# Schematic.net
KiCad netlist of a schematic drawn in EAGLE
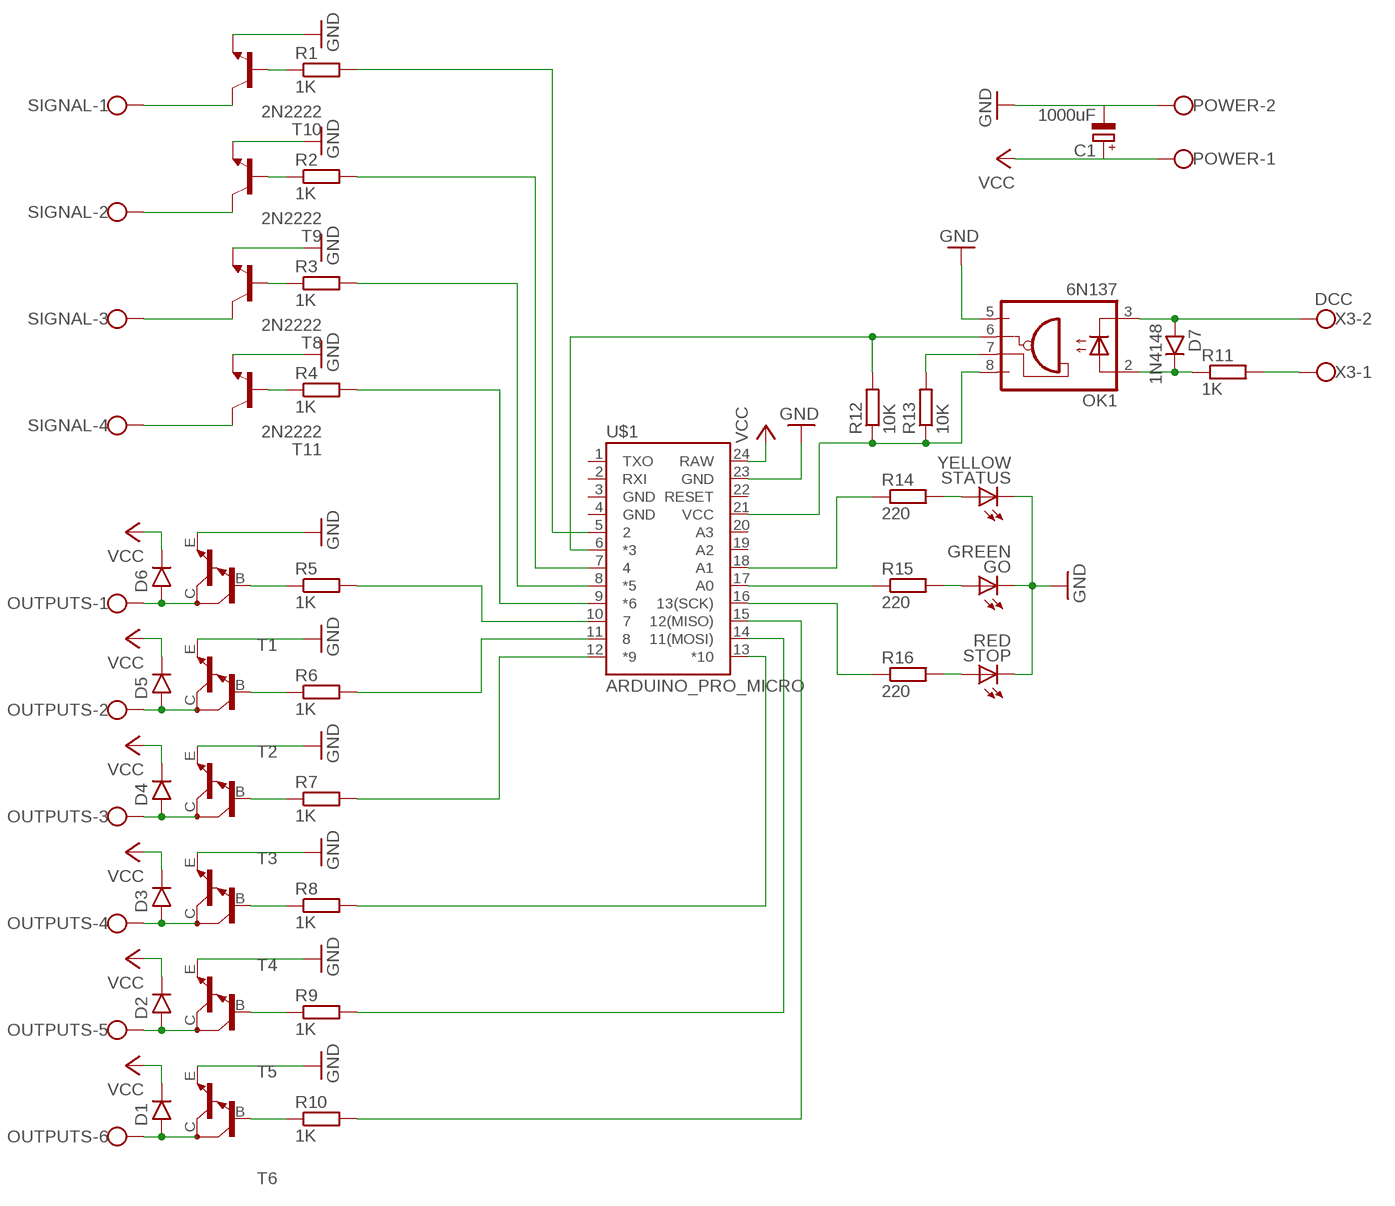
[diagram p0: schematic, sheet 1]

(export (version "E")
  (design (tool "Eeschema 10.0.6"))
  (components
    (comp (ref "C1")
      (value "1000uF")
      (footprint "eagle-import:E5-13")
      (libsource (lib "eagle-import") (part "CPOL-EUE5-13"))
    )
    (comp (ref "D1")
      (value "DO41.3")
      (footprint "eagle-import:DO41-3")
      (libsource (lib "eagle-import") (part "DO41.3"))
    )
    (comp (ref "D2")
      (value "DO41.3")
      (footprint "eagle-import:DO41-3")
      (libsource (lib "eagle-import") (part "DO41.3"))
    )
    (comp (ref "D3")
      (value "DO41.3")
      (footprint "eagle-import:DO41-3")
      (libsource (lib "eagle-import") (part "DO41.3"))
    )
    (comp (ref "D4")
      (value "DO41.3")
      (footprint "eagle-import:DO41-3")
      (libsource (lib "eagle-import") (part "DO41.3"))
    )
    (comp (ref "D5")
      (value "DO41.3")
      (footprint "eagle-import:DO41-3")
      (libsource (lib "eagle-import") (part "DO41.3"))
    )
    (comp (ref "D6")
      (value "DO41.3")
      (footprint "eagle-import:DO41-3")
      (libsource (lib "eagle-import") (part "DO41.3"))
    )
    (comp (ref "D7")
      (value "1N4148")
      (footprint "eagle-import:DO35-3")
      (libsource (lib "eagle-import") (part "1N914.3"))
    )
    (comp (ref "GO")
      (value "GREEN")
      (footprint "eagle-import:LED3MM")
      (libsource (lib "eagle-import") (part "LED3MM"))
    )
    (comp (ref "OK1")
      (value "6N137")
      (footprint "eagle-import:DIL08")
      (libsource (lib "eagle-import") (part "6N137"))
    )
    (comp (ref "OUTPUTS")
      (value "W237-6")
      (footprint "eagle-import:W237-6")
      (libsource (lib "eagle-import") (part "W237-6"))
    )
    (comp (ref "POWER")
      (value "W237-102")
      (footprint "eagle-import:W237-102")
      (fields (field (name "MPN") "237-102"))
      (libsource (lib "eagle-import") (part "W237-102"))
    )
    (comp (ref "R1")
      (value "1K")
      (footprint "eagle-import:0204_7")
      (libsource (lib "eagle-import") (part "R-EU_0204/7"))
    )
    (comp (ref "R2")
      (value "1K")
      (footprint "eagle-import:0204_7")
      (libsource (lib "eagle-import") (part "R-EU_0204/7"))
    )
    (comp (ref "R3")
      (value "1K")
      (footprint "eagle-import:0204_7")
      (libsource (lib "eagle-import") (part "R-EU_0204/7"))
    )
    (comp (ref "R4")
      (value "1K")
      (footprint "eagle-import:0204_7")
      (libsource (lib "eagle-import") (part "R-EU_0204/7"))
    )
    (comp (ref "R5")
      (value "1K")
      (footprint "eagle-import:0204_7")
      (libsource (lib "eagle-import") (part "R-EU_0204/7"))
    )
    (comp (ref "R6")
      (value "1K")
      (footprint "eagle-import:0204_7")
      (libsource (lib "eagle-import") (part "R-EU_0204/7"))
    )
    (comp (ref "R7")
      (value "1K")
      (footprint "eagle-import:0204_7")
      (libsource (lib "eagle-import") (part "R-EU_0204/7"))
    )
    (comp (ref "R8")
      (value "1K")
      (footprint "eagle-import:0204_7")
      (libsource (lib "eagle-import") (part "R-EU_0204/7"))
    )
    (comp (ref "R9")
      (value "1K")
      (footprint "eagle-import:0204_7")
      (libsource (lib "eagle-import") (part "R-EU_0204/7"))
    )
    (comp (ref "R10")
      (value "1K")
      (footprint "eagle-import:0204_7")
      (libsource (lib "eagle-import") (part "R-EU_0204/7"))
    )
    (comp (ref "R11")
      (value "1K")
      (footprint "eagle-import:0204_7")
      (libsource (lib "eagle-import") (part "resistor_R-EU_0204/7"))
    )
    (comp (ref "R12")
      (value "10K")
      (footprint "eagle-import:0204_7")
      (libsource (lib "eagle-import") (part "resistor_R-EU_0204/7"))
    )
    (comp (ref "R13")
      (value "10K")
      (footprint "eagle-import:0204_7")
      (libsource (lib "eagle-import") (part "resistor_R-EU_0204/7"))
    )
    (comp (ref "R14")
      (value "220")
      (footprint "eagle-import:0204_7")
      (libsource (lib "eagle-import") (part "R-EU_0204/7"))
    )
    (comp (ref "R15")
      (value "220")
      (footprint "eagle-import:0204_7")
      (libsource (lib "eagle-import") (part "R-EU_0204/7"))
    )
    (comp (ref "R16")
      (value "220")
      (footprint "eagle-import:0204_7")
      (libsource (lib "eagle-import") (part "R-EU_0204/7"))
    )
    (comp (ref "SIGNAL")
      (value "W237-4")
      (footprint "eagle-import:W237-4")
      (libsource (lib "eagle-import") (part "W237-4"))
    )
    (comp (ref "STATUS")
      (value "YELLOW")
      (footprint "eagle-import:LED3MM")
      (libsource (lib "eagle-import") (part "LED3MM"))
    )
    (comp (ref "STOP")
      (value "RED")
      (footprint "eagle-import:LED3MM")
      (libsource (lib "eagle-import") (part "LED3MM"))
    )
    (comp (ref "T1")
      (value "TIP122VERTICAL")
      (footprint "eagle-import:TO220AV")
      (libsource (lib "eagle-import") (part "TIP122VERTICAL"))
    )
    (comp (ref "T2")
      (value "TIP122VERTICAL")
      (footprint "eagle-import:TO220AV")
      (libsource (lib "eagle-import") (part "TIP122VERTICAL"))
    )
    (comp (ref "T3")
      (value "TIP122VERTICAL")
      (footprint "eagle-import:TO220AV")
      (libsource (lib "eagle-import") (part "TIP122VERTICAL"))
    )
    (comp (ref "T4")
      (value "TIP122VERTICAL")
      (footprint "eagle-import:TO220AV")
      (libsource (lib "eagle-import") (part "TIP122VERTICAL"))
    )
    (comp (ref "T5")
      (value "TIP122VERTICAL")
      (footprint "eagle-import:TO220AV")
      (libsource (lib "eagle-import") (part "TIP122VERTICAL"))
    )
    (comp (ref "T6")
      (value "TIP122VERTICAL")
      (footprint "eagle-import:TO220AV")
      (libsource (lib "eagle-import") (part "TIP122VERTICAL"))
    )
    (comp (ref "T8")
      (value "2N2222")
      (footprint "eagle-import:TO92-EBC")
      (libsource (lib "eagle-import") (part "-NPN-TO92-EBC"))
    )
    (comp (ref "T9")
      (value "2N2222")
      (footprint "eagle-import:TO92-EBC")
      (libsource (lib "eagle-import") (part "-NPN-TO92-EBC"))
    )
    (comp (ref "T10")
      (value "2N2222")
      (footprint "eagle-import:TO92-EBC")
      (libsource (lib "eagle-import") (part "-NPN-TO92-EBC"))
    )
    (comp (ref "T11")
      (value "2N2222")
      (footprint "eagle-import:TO92-EBC")
      (libsource (lib "eagle-import") (part "-NPN-TO92-EBC"))
    )
    (comp (ref "U$1")
      (value "ARDUINO_PRO_MICRO")
      (footprint "eagle-import:ARDUINO_PRO_MICRO")
      (libsource (lib "eagle-import") (part "ARDUINO_PRO_MICRO"))
    )
    (comp (ref "X3")
      (value "DCC")
      (footprint "eagle-import:W237-102")
      (fields (field (name "MPN") "237-102"))
      (libsource (lib "eagle-import") (part "W237-102"))
    )
  )
  (nets
    (net (code "1") (name "GND") (class "Default")
      (node (ref "C1") (pin "-") (pinfunction "-_-") (pintype "passive"))
      (node (ref "GO") (pin "K") (pinfunction "C_K") (pintype "passive"))
      (node (ref "OK1") (pin "5") (pinfunction "GND_5") (pintype "passive"))
      (node (ref "POWER") (pin "2") (pinfunction "KL_2") (pintype "passive"))
      (node (ref "STATUS") (pin "K") (pinfunction "C_K") (pintype "passive"))
      (node (ref "STOP") (pin "K") (pinfunction "C_K") (pintype "passive"))
      (node (ref "T1") (pin "E") (pinfunction "E_E") (pintype "passive"))
      (node (ref "T10") (pin "E") (pinfunction "E_E") (pintype "passive"))
      (node (ref "T11") (pin "E") (pinfunction "E_E") (pintype "passive"))
      (node (ref "T2") (pin "E") (pinfunction "E_E") (pintype "passive"))
      (node (ref "T3") (pin "E") (pinfunction "E_E") (pintype "passive"))
      (node (ref "T4") (pin "E") (pinfunction "E_E") (pintype "passive"))
      (node (ref "T5") (pin "E") (pinfunction "E_E") (pintype "passive"))
      (node (ref "T6") (pin "E") (pinfunction "E_E") (pintype "passive"))
      (node (ref "T8") (pin "E") (pinfunction "E_E") (pintype "passive"))
      (node (ref "T9") (pin "E") (pinfunction "E_E") (pintype "passive"))
      (node (ref "U$1") (pin "23") (pinfunction "GND_23") (pintype "bidirectional"))
    )
    (net (code "2") (name "Net-(GO-PadA)") (class "Default")
      (node (ref "GO") (pin "A") (pinfunction "A_A") (pintype "passive"))
      (node (ref "R15") (pin "2") (pinfunction "2_2") (pintype "passive"))
    )
    (net (code "3") (name "Net-(OK1-A)") (class "Default")
      (node (ref "D7") (pin "C") (pinfunction "C_C") (pintype "passive"))
      (node (ref "OK1") (pin "2") (pinfunction "A_2") (pintype "passive"))
      (node (ref "R11") (pin "1") (pinfunction "1_1") (pintype "passive"))
    )
    (net (code "4") (name "Net-(OK1-C)") (class "Default")
      (node (ref "D7") (pin "A") (pinfunction "A_A") (pintype "passive"))
      (node (ref "OK1") (pin "3") (pinfunction "C_3") (pintype "passive"))
      (node (ref "X3") (pin "2") (pinfunction "KL_2") (pintype "passive"))
    )
    (net (code "5") (name "Net-(OK1-VCC)") (class "Default")
      (node (ref "OK1") (pin "8") (pinfunction "VCC_8") (pintype "passive"))
      (node (ref "R12") (pin "1") (pinfunction "1_1") (pintype "passive"))
      (node (ref "R13") (pin "1") (pinfunction "1_1") (pintype "passive"))
      (node (ref "U$1") (pin "21") (pinfunction "VCC_21") (pintype "bidirectional"))
    )
    (net (code "6") (name "Net-(OK1-VE)") (class "Default")
      (node (ref "OK1") (pin "7") (pinfunction "VE_7") (pintype "passive"))
      (node (ref "R13") (pin "2") (pinfunction "2_2") (pintype "passive"))
    )
    (net (code "7") (name "Net-(OK1-VO)") (class "Default")
      (node (ref "OK1") (pin "6") (pinfunction "VO_6") (pintype "passive"))
      (node (ref "R12") (pin "2") (pinfunction "2_2") (pintype "passive"))
      (node (ref "U$1") (pin "6") (pinfunction "*3_6") (pintype "bidirectional"))
    )
    (net (code "8") (name "Net-(OUTPUTSA-KL)") (class "Default")
      (node (ref "D6") (pin "A") (pinfunction "A_A") (pintype "passive"))
      (node (ref "OUTPUTS") (pin "1") (pinfunction "KL_1") (pintype "passive"))
      (node (ref "T1") (pin "C") (pinfunction "C_C") (pintype "passive"))
    )
    (net (code "9") (name "Net-(OUTPUTSB-KL)") (class "Default")
      (node (ref "D5") (pin "A") (pinfunction "A_A") (pintype "passive"))
      (node (ref "OUTPUTS") (pin "2") (pinfunction "KL_2") (pintype "passive"))
      (node (ref "T2") (pin "C") (pinfunction "C_C") (pintype "passive"))
    )
    (net (code "10") (name "Net-(OUTPUTSC-KL)") (class "Default")
      (node (ref "D4") (pin "A") (pinfunction "A_A") (pintype "passive"))
      (node (ref "OUTPUTS") (pin "3") (pinfunction "KL_3") (pintype "passive"))
      (node (ref "T3") (pin "C") (pinfunction "C_C") (pintype "passive"))
    )
    (net (code "11") (name "Net-(OUTPUTSD-KL)") (class "Default")
      (node (ref "D3") (pin "A") (pinfunction "A_A") (pintype "passive"))
      (node (ref "OUTPUTS") (pin "4") (pinfunction "KL_4") (pintype "passive"))
      (node (ref "T4") (pin "C") (pinfunction "C_C") (pintype "passive"))
    )
    (net (code "12") (name "Net-(OUTPUTSE-KL)") (class "Default")
      (node (ref "D2") (pin "A") (pinfunction "A_A") (pintype "passive"))
      (node (ref "OUTPUTS") (pin "5") (pinfunction "KL_5") (pintype "passive"))
      (node (ref "T5") (pin "C") (pinfunction "C_C") (pintype "passive"))
    )
    (net (code "13") (name "Net-(OUTPUTSF-KL)") (class "Default")
      (node (ref "D1") (pin "A") (pinfunction "A_A") (pintype "passive"))
      (node (ref "OUTPUTS") (pin "6") (pinfunction "KL_6") (pintype "passive"))
      (node (ref "T6") (pin "C") (pinfunction "C_C") (pintype "passive"))
    )
    (net (code "14") (name "Net-(R1-Pad1)") (class "Default")
      (node (ref "R1") (pin "1") (pinfunction "1_1") (pintype "passive"))
      (node (ref "T10") (pin "B") (pinfunction "B_B") (pintype "passive"))
    )
    (net (code "15") (name "Net-(R2-Pad1)") (class "Default")
      (node (ref "R2") (pin "1") (pinfunction "1_1") (pintype "passive"))
      (node (ref "T9") (pin "B") (pinfunction "B_B") (pintype "passive"))
    )
    (net (code "16") (name "Net-(R3-Pad1)") (class "Default")
      (node (ref "R3") (pin "1") (pinfunction "1_1") (pintype "passive"))
      (node (ref "T8") (pin "B") (pinfunction "B_B") (pintype "passive"))
    )
    (net (code "17") (name "Net-(R4-Pad1)") (class "Default")
      (node (ref "R4") (pin "1") (pinfunction "1_1") (pintype "passive"))
      (node (ref "T11") (pin "B") (pinfunction "B_B") (pintype "passive"))
    )
    (net (code "18") (name "Net-(R5-Pad1)") (class "Default")
      (node (ref "R5") (pin "1") (pinfunction "1_1") (pintype "passive"))
      (node (ref "T1") (pin "B") (pinfunction "B_B") (pintype "passive"))
    )
    (net (code "19") (name "Net-(R6-Pad1)") (class "Default")
      (node (ref "R6") (pin "1") (pinfunction "1_1") (pintype "passive"))
      (node (ref "T2") (pin "B") (pinfunction "B_B") (pintype "passive"))
    )
    (net (code "20") (name "Net-(R7-Pad1)") (class "Default")
      (node (ref "R7") (pin "1") (pinfunction "1_1") (pintype "passive"))
      (node (ref "T3") (pin "B") (pinfunction "B_B") (pintype "passive"))
    )
    (net (code "21") (name "Net-(R8-Pad1)") (class "Default")
      (node (ref "R8") (pin "1") (pinfunction "1_1") (pintype "passive"))
      (node (ref "T4") (pin "B") (pinfunction "B_B") (pintype "passive"))
    )
    (net (code "22") (name "Net-(R9-Pad1)") (class "Default")
      (node (ref "R9") (pin "1") (pinfunction "1_1") (pintype "passive"))
      (node (ref "T5") (pin "B") (pinfunction "B_B") (pintype "passive"))
    )
    (net (code "23") (name "Net-(R10-Pad1)") (class "Default")
      (node (ref "R10") (pin "1") (pinfunction "1_1") (pintype "passive"))
      (node (ref "T6") (pin "B") (pinfunction "B_B") (pintype "passive"))
    )
    (net (code "24") (name "Net-(R14-Pad2)") (class "Default")
      (node (ref "R14") (pin "2") (pinfunction "2_2") (pintype "passive"))
      (node (ref "STATUS") (pin "A") (pinfunction "A_A") (pintype "passive"))
    )
    (net (code "25") (name "Net-(R16-Pad2)") (class "Default")
      (node (ref "R16") (pin "2") (pinfunction "2_2") (pintype "passive"))
      (node (ref "STOP") (pin "A") (pinfunction "A_A") (pintype "passive"))
    )
    (net (code "26") (name "Net-(SIGNALA-KL)") (class "Default")
      (node (ref "SIGNAL") (pin "1") (pinfunction "KL_1") (pintype "passive"))
      (node (ref "T10") (pin "C") (pinfunction "C_C") (pintype "passive"))
    )
    (net (code "27") (name "Net-(SIGNALB-KL)") (class "Default")
      (node (ref "SIGNAL") (pin "2") (pinfunction "KL_2") (pintype "passive"))
      (node (ref "T9") (pin "C") (pinfunction "C_C") (pintype "passive"))
    )
    (net (code "28") (name "Net-(SIGNALC-KL)") (class "Default")
      (node (ref "SIGNAL") (pin "3") (pinfunction "KL_3") (pintype "passive"))
      (node (ref "T8") (pin "C") (pinfunction "C_C") (pintype "passive"))
    )
    (net (code "29") (name "Net-(SIGNALD-KL)") (class "Default")
      (node (ref "SIGNAL") (pin "4") (pinfunction "KL_4") (pintype "passive"))
      (node (ref "T11") (pin "C") (pinfunction "C_C") (pintype "passive"))
    )
    (net (code "30") (name "Net-(U$1-*5)") (class "Default")
      (node (ref "R3") (pin "2") (pinfunction "2_2") (pintype "passive"))
      (node (ref "U$1") (pin "8") (pinfunction "*5_8") (pintype "bidirectional"))
    )
    (net (code "31") (name "Net-(U$1-*6)") (class "Default")
      (node (ref "R4") (pin "2") (pinfunction "2_2") (pintype "passive"))
      (node (ref "U$1") (pin "9") (pinfunction "*6_9") (pintype "bidirectional"))
    )
    (net (code "32") (name "Net-(U$1-*9)") (class "Default")
      (node (ref "R7") (pin "2") (pinfunction "2_2") (pintype "passive"))
      (node (ref "U$1") (pin "12") (pinfunction "*9_12") (pintype "bidirectional"))
    )
    (net (code "33") (name "Net-(U$1-*10)") (class "Default")
      (node (ref "R8") (pin "2") (pinfunction "2_2") (pintype "passive"))
      (node (ref "U$1") (pin "13") (pinfunction "*10_13") (pintype "bidirectional"))
    )
    (net (code "34") (name "Net-(U$1-2)") (class "Default")
      (node (ref "R1") (pin "2") (pinfunction "2_2") (pintype "passive"))
      (node (ref "U$1") (pin "5") (pinfunction "2_5") (pintype "bidirectional"))
    )
    (net (code "35") (name "Net-(U$1-4)") (class "Default")
      (node (ref "R2") (pin "2") (pinfunction "2_2") (pintype "passive"))
      (node (ref "U$1") (pin "7") (pinfunction "4_7") (pintype "bidirectional"))
    )
    (net (code "36") (name "Net-(U$1-7)") (class "Default")
      (node (ref "R5") (pin "2") (pinfunction "2_2") (pintype "passive"))
      (node (ref "U$1") (pin "10") (pinfunction "7_10") (pintype "bidirectional"))
    )
    (net (code "37") (name "Net-(U$1-8)") (class "Default")
      (node (ref "R6") (pin "2") (pinfunction "2_2") (pintype "passive"))
      (node (ref "U$1") (pin "11") (pinfunction "8_11") (pintype "bidirectional"))
    )
    (net (code "38") (name "Net-(U$1-11(MOSI))") (class "Default")
      (node (ref "R9") (pin "2") (pinfunction "2_2") (pintype "passive"))
      (node (ref "U$1") (pin "14") (pinfunction "11(MOSI)_14") (pintype "bidirectional"))
    )
    (net (code "39") (name "Net-(U$1-12(MISO))") (class "Default")
      (node (ref "R10") (pin "2") (pinfunction "2_2") (pintype "passive"))
      (node (ref "U$1") (pin "15") (pinfunction "12(MISO)_15") (pintype "bidirectional"))
    )
    (net (code "40") (name "Net-(U$1-13(SCK))") (class "Default")
      (node (ref "R16") (pin "1") (pinfunction "1_1") (pintype "passive"))
      (node (ref "U$1") (pin "16") (pinfunction "13(SCK)_16") (pintype "bidirectional"))
    )
    (net (code "41") (name "Net-(U$1-A0)") (class "Default")
      (node (ref "R15") (pin "1") (pinfunction "1_1") (pintype "passive"))
      (node (ref "U$1") (pin "17") (pinfunction "A0_17") (pintype "bidirectional"))
    )
    (net (code "42") (name "Net-(U$1-A1)") (class "Default")
      (node (ref "R14") (pin "1") (pinfunction "1_1") (pintype "passive"))
      (node (ref "U$1") (pin "18") (pinfunction "A1_18") (pintype "bidirectional"))
    )
    (net (code "43") (name "Net-(X3A-KL)") (class "Default")
      (node (ref "R11") (pin "2") (pinfunction "2_2") (pintype "passive"))
      (node (ref "X3") (pin "1") (pinfunction "KL_1") (pintype "passive"))
    )
    (net (code "44") (name "VCC") (class "Default")
      (node (ref "C1") (pin "+") (pinfunction "+_+") (pintype "passive"))
      (node (ref "D1") (pin "C") (pinfunction "C_C") (pintype "passive"))
      (node (ref "D2") (pin "C") (pinfunction "C_C") (pintype "passive"))
      (node (ref "D3") (pin "C") (pinfunction "C_C") (pintype "passive"))
      (node (ref "D4") (pin "C") (pinfunction "C_C") (pintype "passive"))
      (node (ref "D5") (pin "C") (pinfunction "C_C") (pintype "passive"))
      (node (ref "D6") (pin "C") (pinfunction "C_C") (pintype "passive"))
      (node (ref "POWER") (pin "1") (pinfunction "KL_1") (pintype "passive"))
      (node (ref "U$1") (pin "24") (pinfunction "RAW_24") (pintype "bidirectional"))
    )
    (net (code "45") (name "unconnected-(U$1-A2-Pad19)") (class "Default")
      (node (ref "U$1") (pin "19") (pinfunction "A2_19") (pintype "bidirectional"))
    )
    (net (code "46") (name "unconnected-(U$1-A3-Pad20)") (class "Default")
      (node (ref "U$1") (pin "20") (pinfunction "A3_20") (pintype "bidirectional"))
    )
    (net (code "47") (name "unconnected-(U$1-GND-Pad3)") (class "Default")
      (node (ref "U$1") (pin "3") (pinfunction "GND_3") (pintype "bidirectional"))
    )
    (net (code "48") (name "unconnected-(U$1-GND-Pad4)") (class "Default")
      (node (ref "U$1") (pin "4") (pinfunction "GND_4") (pintype "bidirectional"))
    )
    (net (code "49") (name "unconnected-(U$1-RESET-Pad22)") (class "Default")
      (node (ref "U$1") (pin "22") (pinfunction "RESET_22") (pintype "bidirectional"))
    )
    (net (code "50") (name "unconnected-(U$1-RXI-Pad2)") (class "Default")
      (node (ref "U$1") (pin "2") (pinfunction "RXI_2") (pintype "bidirectional"))
    )
    (net (code "51") (name "unconnected-(U$1-TXO-Pad1)") (class "Default")
      (node (ref "U$1") (pin "1") (pinfunction "TXO_1") (pintype "bidirectional"))
    )
  )
)
